# MAX17048.net
KiCad netlist of a schematic drawn in Altium Designer
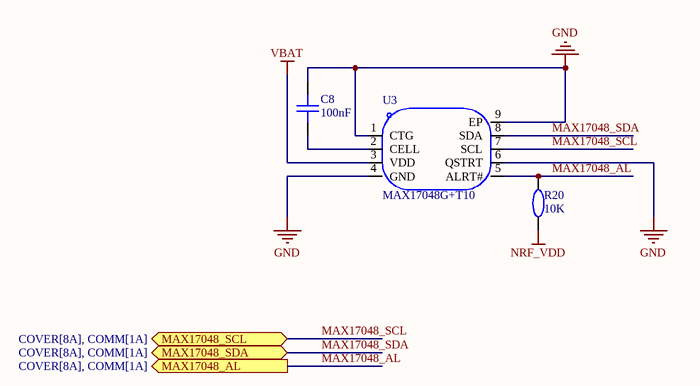
[diagram p0: MAX17048.SchDoc]

(export (version "E")
  (design (tool "Eeschema 10.0.6"))
  (components
    (comp (ref "C8")
      (value "100nF")
      (footprint "C0402")
      (fields (field (name "NAME") "100nF"))
      (libsource (lib "my_library") (part "CAP_0402"))
    )
    (comp (ref "R20")
      (value "10K")
      (footprint "R0402")
      (fields (field (name "NAME") "10K"))
      (libsource (lib "my_library") (part "Res_0402"))
    )
    (comp (ref "U3")
      (value "MAX17048G+T10")
      (footprint "DFN-8_L2.0-W2.0-P0.50-BL-EP")
      (fields (field (name "MANUFACTURER") "ADI(亚德诺)/MAXIM(美信)") (field (name "NAME") "MAX17048G+T10"))
      (libsource (lib "my_library") (part "MAX17048G+T10"))
    )
  )
  (nets
    (net (code "1") (name "/MAX17048_AL") (class "Default")
      (node (ref "R20") (pin "2") (pinfunction "2_2") (pintype "passive"))
      (node (ref "U3") (pin "5") (pinfunction "ALRT#_5") (pintype "passive"))
    )
    (net (code "2") (name "/MAX17048_SCL") (class "Default")
      (node (ref "U3") (pin "7") (pinfunction "SCL_7") (pintype "passive"))
    )
    (net (code "3") (name "/MAX17048_SDA") (class "Default")
      (node (ref "U3") (pin "8") (pinfunction "SDA_8") (pintype "passive"))
    )
    (net (code "4") (name "GND") (class "Default")
      (node (ref "C8") (pin "2") (pinfunction "2_2") (pintype "passive"))
      (node (ref "U3") (pin "1") (pinfunction "CTG_1") (pintype "passive"))
      (node (ref "U3") (pin "4") (pinfunction "GND_4") (pintype "passive"))
      (node (ref "U3") (pin "6") (pinfunction "QSTRT_6") (pintype "passive"))
      (node (ref "U3") (pin "9") (pinfunction "EP_9") (pintype "passive"))
    )
    (net (code "5") (name "NRF_VDD") (class "Default")
      (node (ref "R20") (pin "1") (pinfunction "1_1") (pintype "passive"))
    )
    (net (code "6") (name "Net-(U3-CELL)") (class "Default")
      (node (ref "C8") (pin "1") (pinfunction "1_1") (pintype "passive"))
      (node (ref "U3") (pin "2") (pinfunction "CELL_2") (pintype "passive"))
    )
    (net (code "7") (name "VBAT") (class "Default")
      (node (ref "U3") (pin "3") (pinfunction "VDD_3") (pintype "passive"))
    )
  )
)
